# untitled.net
KiCad netlist of a schematic drawn in EAGLE
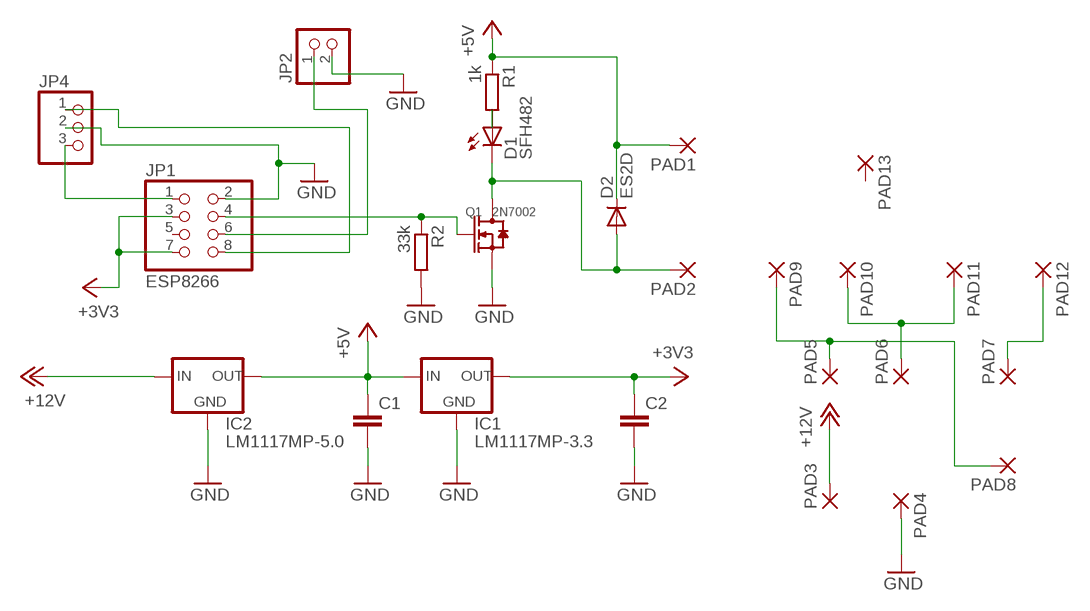
[diagram p0: schematic, sheet 1]

(export (version "E")
  (design (tool "Eeschema 10.0.6"))
  (components
    (comp (ref "C1")
      (value "C-EUC1812")
      (footprint "eagle-import:C1812")
      (libsource (lib "eagle-import") (part "C-EUC1812"))
    )
    (comp (ref "C2")
      (value "C-EUC1812")
      (footprint "eagle-import:C1812")
      (libsource (lib "eagle-import") (part "C-EUC1812"))
    )
    (comp (ref "D1")
      (value "SFH482")
      (footprint "eagle-import:SFH482")
      (libsource (lib "eagle-import") (part "SFH482"))
    )
    (comp (ref "D2")
      (value "ES2D")
      (footprint "eagle-import:SMB")
      (libsource (lib "eagle-import") (part "ES2D"))
    )
    (comp (ref "IC1")
      (value "LM1117MP-3.3")
      (footprint "eagle-import:SOT223")
      (fields (field (name "MF") "Texas Instruments"))
      (libsource (lib "eagle-import") (part "LM1117?-MP3.3"))
    )
    (comp (ref "IC2")
      (value "LM1117MP-5.0")
      (footprint "eagle-import:SOT223")
      (fields (field (name "MF") "Texas Instruments"))
      (libsource (lib "eagle-import") (part "LM1117?-MP5.0"))
    )
    (comp (ref "JP1")
      (value "ESP8266")
      (footprint "eagle-import:2X04")
      (libsource (lib "eagle-import") (part "PINHD-2X4"))
    )
    (comp (ref "JP2")
      (value "PINHD-1X2")
      (footprint "eagle-import:1X02")
      (libsource (lib "eagle-import") (part "PINHD-1X2"))
    )
    (comp (ref "JP4")
      (value "PINHD-1X3")
      (footprint "eagle-import:1X03")
      (libsource (lib "eagle-import") (part "PINHD-1X3"))
    )
    (comp (ref "PAD1")
      (value "3,17/1,1")
      (footprint "eagle-import:3,17_1,1")
      (libsource (lib "eagle-import") (part "3,17/1,1"))
    )
    (comp (ref "PAD2")
      (value "3,17/1,1")
      (footprint "eagle-import:3,17_1,1")
      (libsource (lib "eagle-import") (part "3,17/1,1"))
    )
    (comp (ref "PAD3")
      (value "3,17/1,1")
      (footprint "eagle-import:3,17_1,1")
      (libsource (lib "eagle-import") (part "3,17/1,1"))
    )
    (comp (ref "PAD4")
      (value "3,17/1,1")
      (footprint "eagle-import:3,17_1,1")
      (libsource (lib "eagle-import") (part "3,17/1,1"))
    )
    (comp (ref "PAD5")
      (value "3,17/1,1")
      (footprint "eagle-import:3,17_1,1")
      (libsource (lib "eagle-import") (part "3,17/1,1"))
    )
    (comp (ref "PAD6")
      (value "3,17/1,1")
      (footprint "eagle-import:3,17_1,1")
      (libsource (lib "eagle-import") (part "3,17/1,1"))
    )
    (comp (ref "PAD7")
      (value "3,17/1,1")
      (footprint "eagle-import:3,17_1,1")
      (libsource (lib "eagle-import") (part "3,17/1,1"))
    )
    (comp (ref "PAD8")
      (value "3,17/1,1")
      (footprint "eagle-import:3,17_1,1")
      (libsource (lib "eagle-import") (part "3,17/1,1"))
    )
    (comp (ref "PAD9")
      (value "3,17/1,1")
      (footprint "eagle-import:3,17_1,1")
      (libsource (lib "eagle-import") (part "3,17/1,1"))
    )
    (comp (ref "PAD10")
      (value "3,17/1,1")
      (footprint "eagle-import:3,17_1,1")
      (libsource (lib "eagle-import") (part "3,17/1,1"))
    )
    (comp (ref "PAD11")
      (value "3,17/1,1")
      (footprint "eagle-import:3,17_1,1")
      (libsource (lib "eagle-import") (part "3,17/1,1"))
    )
    (comp (ref "PAD12")
      (value "3,17/1,1")
      (footprint "eagle-import:3,17_1,1")
      (libsource (lib "eagle-import") (part "3,17/1,1"))
    )
    (comp (ref "PAD13")
      (value "3,17/1,1")
      (footprint "eagle-import:3,17_1,1")
      (libsource (lib "eagle-import") (part "3,17/1,1"))
    )
    (comp (ref "Q1")
      (value "2N7002")
      (footprint "eagle-import:SOT-23")
      (fields (field (name "MPN") "2N7002,215"))
      (libsource (lib "eagle-import") (part "SMD-MOSFET-N-CH-60V-300MA-LOGIC-LEVEL-FET-2N7002(SOT-23)"))
    )
    (comp (ref "R1")
      (value "1k")
      (footprint "eagle-import:M0805")
      (libsource (lib "eagle-import") (part "R-EU_M0805"))
    )
    (comp (ref "R2")
      (value "33k")
      (footprint "eagle-import:M0805")
      (libsource (lib "eagle-import") (part "R-EU_M0805"))
    )
  )
  (nets
    (net (code "1") (name "+3V3") (class "Default")
      (node (ref "C2") (pin "1") (pinfunction "1_1") (pintype "passive"))
      (node (ref "IC1") (pin "2") (pinfunction "OUT_2") (pintype "passive"))
      (node (ref "IC1") (pin "4") (pinfunction "OUT_4") (pintype "passive"))
      (node (ref "JP1") (pin "3") (pinfunction "3_3") (pintype "passive"))
      (node (ref "JP1") (pin "7") (pinfunction "7_7") (pintype "passive"))
    )
    (net (code "2") (name "+5V") (class "Default")
      (node (ref "C1") (pin "1") (pinfunction "1_1") (pintype "passive"))
      (node (ref "D2") (pin "C") (pinfunction "C_C") (pintype "passive"))
      (node (ref "IC1") (pin "3") (pinfunction "IN_3") (pintype "input"))
      (node (ref "IC2") (pin "2") (pinfunction "OUT_2") (pintype "passive"))
      (node (ref "IC2") (pin "4") (pinfunction "OUT_4") (pintype "passive"))
      (node (ref "PAD1") (pin "1") (pinfunction "P_1") (pintype "passive"))
      (node (ref "R1") (pin "1") (pinfunction "1_1") (pintype "passive"))
    )
    (net (code "3") (name "+12V") (class "Default")
      (node (ref "IC2") (pin "3") (pinfunction "IN_3") (pintype "input"))
      (node (ref "PAD3") (pin "1") (pinfunction "P_1") (pintype "passive"))
    )
    (net (code "4") (name "GND") (class "Default")
      (node (ref "C1") (pin "2") (pinfunction "2_2") (pintype "passive"))
      (node (ref "C2") (pin "2") (pinfunction "2_2") (pintype "passive"))
      (node (ref "IC1") (pin "1") (pinfunction "GND_1") (pintype "input"))
      (node (ref "IC2") (pin "1") (pinfunction "GND_1") (pintype "input"))
      (node (ref "JP1") (pin "2") (pinfunction "2_2") (pintype "passive"))
      (node (ref "JP2") (pin "2") (pinfunction "2_2") (pintype "passive"))
      (node (ref "JP4") (pin "2") (pinfunction "2_2") (pintype "passive"))
      (node (ref "PAD4") (pin "1") (pinfunction "P_1") (pintype "passive"))
      (node (ref "Q1") (pin "2") (pinfunction "S_2") (pintype "passive"))
      (node (ref "R2") (pin "2") (pinfunction "2_2") (pintype "passive"))
    )
    (net (code "5") (name "Net-(D1-C)") (class "Default")
      (node (ref "D1") (pin "K") (pinfunction "C_K") (pintype "passive"))
      (node (ref "D2") (pin "A") (pinfunction "A_A") (pintype "passive"))
      (node (ref "PAD2") (pin "1") (pinfunction "P_1") (pintype "passive"))
      (node (ref "Q1") (pin "3") (pinfunction "D_3") (pintype "passive"))
    )
    (net (code "6") (name "Net-(D1-PadA)") (class "Default")
      (node (ref "D1") (pin "A") (pinfunction "A_A") (pintype "passive"))
      (node (ref "R1") (pin "2") (pinfunction "2_2") (pintype "passive"))
    )
    (net (code "7") (name "Net-(JP1-Pad1)") (class "Default")
      (node (ref "JP1") (pin "1") (pinfunction "1_1") (pintype "passive"))
      (node (ref "JP4") (pin "3") (pinfunction "3_3") (pintype "passive"))
    )
    (net (code "8") (name "Net-(JP1-Pad6)") (class "Default")
      (node (ref "JP1") (pin "6") (pinfunction "6_6") (pintype "passive"))
      (node (ref "JP2") (pin "1") (pinfunction "1_1") (pintype "passive"))
    )
    (net (code "9") (name "Net-(JP1-Pad8)") (class "Default")
      (node (ref "JP1") (pin "8") (pinfunction "8_8") (pintype "passive"))
      (node (ref "JP4") (pin "1") (pinfunction "1_1") (pintype "passive"))
    )
    (net (code "10") (name "Net-(PAD5-P)") (class "Default")
      (node (ref "PAD5") (pin "1") (pinfunction "P_1") (pintype "passive"))
      (node (ref "PAD8") (pin "1") (pinfunction "P_1") (pintype "passive"))
      (node (ref "PAD9") (pin "1") (pinfunction "P_1") (pintype "passive"))
    )
    (net (code "11") (name "Net-(PAD10-P)") (class "Default")
      (node (ref "PAD10") (pin "1") (pinfunction "P_1") (pintype "passive"))
      (node (ref "PAD11") (pin "1") (pinfunction "P_1") (pintype "passive"))
      (node (ref "PAD6") (pin "1") (pinfunction "P_1") (pintype "passive"))
    )
    (net (code "12") (name "Net-(PAD12-P)") (class "Default")
      (node (ref "PAD12") (pin "1") (pinfunction "P_1") (pintype "passive"))
      (node (ref "PAD7") (pin "1") (pinfunction "P_1") (pintype "passive"))
    )
    (net (code "13") (name "Net-(Q1-G)") (class "Default")
      (node (ref "JP1") (pin "4") (pinfunction "4_4") (pintype "passive"))
      (node (ref "Q1") (pin "1") (pinfunction "G_1") (pintype "passive"))
      (node (ref "R2") (pin "1") (pinfunction "1_1") (pintype "passive"))
    )
    (net (code "14") (name "unconnected-(JP1-Pad5)") (class "Default")
      (node (ref "JP1") (pin "5") (pinfunction "5_5") (pintype "passive"))
    )
    (net (code "15") (name "unconnected-(PAD13-P-Pad1)") (class "Default")
      (node (ref "PAD13") (pin "1") (pinfunction "P_1") (pintype "passive"))
    )
  )
)
